# placa1.net
KiCad netlist of a schematic drawn in Altium Designer
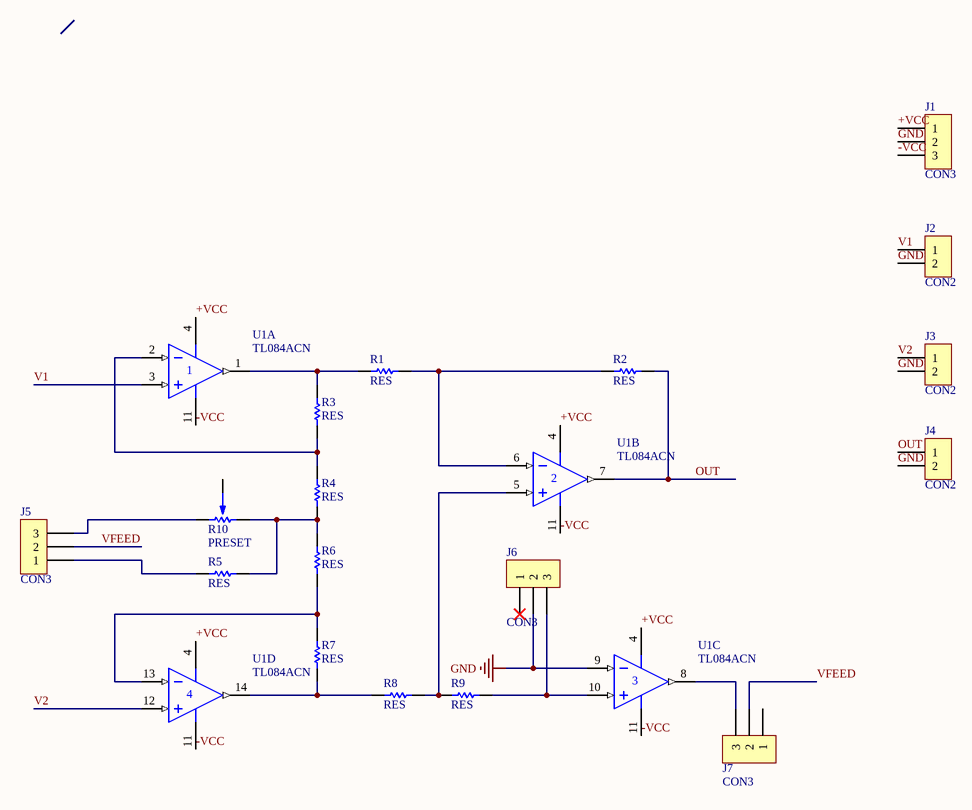
[diagram p0: placa1.SchDoc]

(export (version "E")
  (design (tool "Eeschema 10.0.6"))
  (components
    (comp (ref "J1") (value "CON3") (footprint "SIP3") (libsource (lib "LIBEBAL") (part "CON3")))
    (comp (ref "J2") (value "CON2") (footprint "SIP2") (libsource (lib "LIBEBAL") (part "CON2")))
    (comp (ref "J3") (value "CON2") (footprint "SIP2") (libsource (lib "LIBEBAL") (part "CON2")))
    (comp (ref "J4") (value "CON2") (footprint "SIP2") (libsource (lib "LIBEBAL") (part "CON2")))
    (comp (ref "J5") (value "CON3") (footprint "SIP3") (libsource (lib "") (part "CON3_2")))
    (comp (ref "J6") (value "CON3") (footprint "SIP3") (libsource (lib "") (part "CON3_3")))
    (comp (ref "J7") (value "CON3") (footprint "SIP3") (libsource (lib "") (part "CON3_1")))
    (comp (ref "R1") (value "RES") (footprint "0805") (libsource (lib "LIBEBAL") (part "RES")))
    (comp (ref "R2") (value "RES") (footprint "0805") (libsource (lib "LIBEBAL") (part "RES")))
    (comp (ref "R3") (value "RES") (footprint "0805") (libsource (lib "LIBEBAL") (part "RES")))
    (comp (ref "R4") (value "RES") (footprint "0805") (libsource (lib "LIBEBAL") (part "RES")))
    (comp (ref "R5") (value "RES") (footprint "0805") (libsource (lib "LIBEBAL") (part "RES")))
    (comp (ref "R6") (value "RES") (footprint "0805") (libsource (lib "LIBEBAL") (part "RES")))
    (comp (ref "R7") (value "RES") (footprint "0805") (libsource (lib "LIBEBAL") (part "RES")))
    (comp (ref "R8") (value "RES") (footprint "0805") (libsource (lib "LIBEBAL") (part "RES")))
    (comp (ref "R9") (value "RES") (footprint "0805") (libsource (lib "LIBEBAL") (part "RES")))
    (comp (ref "R10") (value "PRESET") (footprint "PRESET V") (libsource (lib "LIBEBAL") (part "PRESET")))
    (comp (ref "U1")
      (value "TL084ACN")
      (footprint "646-06")
      (description "JFET-Input Operational Amplifier")
      (fields (field (name "PUBLISHER") "Altium Limited"))
      (libsource (lib "Motorola Amplifier Operational Amplifier") (part "TL084ACN"))
    )
  )
  (nets
    (net (code "1") (name "/+VCC") (class "Default")
      (node (ref "J1") (pin "1") (pinfunction "1_1") (pintype "passive"))
      (node (ref "U1") (pin "4") (pinfunction "V+_4") (pintype "power_in"))
    )
    (net (code "2") (name "/-VCC") (class "Default")
      (node (ref "J1") (pin "3") (pinfunction "3_3") (pintype "passive"))
      (node (ref "U1") (pin "11") (pinfunction "V-_11") (pintype "power_in"))
    )
    (net (code "3") (name "/OUT") (class "Default")
      (node (ref "J4") (pin "1") (pinfunction "1_1") (pintype "passive"))
      (node (ref "R2") (pin "2") (pinfunction "2_2") (pintype "passive"))
      (node (ref "U1") (pin "7") (pinfunction "OUT_7") (pintype "output"))
    )
    (net (code "4") (name "/V1") (class "Default")
      (node (ref "J2") (pin "1") (pinfunction "1_1") (pintype "passive"))
      (node (ref "U1") (pin "3") (pinfunction "IN+_3") (pintype "input"))
    )
    (net (code "5") (name "/V2") (class "Default")
      (node (ref "J3") (pin "1") (pinfunction "1_1") (pintype "passive"))
      (node (ref "U1") (pin "12") (pinfunction "IN+_12") (pintype "input"))
    )
    (net (code "6") (name "/VFEED") (class "Default")
      (node (ref "J5") (pin "2") (pinfunction "2_2") (pintype "passive"))
      (node (ref "J7") (pin "2") (pinfunction "2_2") (pintype "passive"))
    )
    (net (code "7") (name "GND") (class "Default")
      (node (ref "J1") (pin "2") (pinfunction "2_2") (pintype "passive"))
      (node (ref "J2") (pin "2") (pinfunction "2_2") (pintype "passive"))
      (node (ref "J3") (pin "2") (pinfunction "2_2") (pintype "passive"))
      (node (ref "J4") (pin "2") (pinfunction "2_2") (pintype "passive"))
      (node (ref "J6") (pin "2") (pinfunction "2_2") (pintype "passive"))
      (node (ref "U1") (pin "9") (pinfunction "IN-_9") (pintype "input"))
    )
    (net (code "8") (name "Net-(J5-Pad1)") (class "Default")
      (node (ref "J5") (pin "1") (pinfunction "1_1") (pintype "passive"))
      (node (ref "R5") (pin "1") (pinfunction "1_1") (pintype "passive"))
    )
    (net (code "9") (name "Net-(J5-Pad3)") (class "Default")
      (node (ref "J5") (pin "3") (pinfunction "3_3") (pintype "passive"))
      (node (ref "R10") (pin "1") (pinfunction "1_1") (pintype "passive"))
    )
    (net (code "10") (name "Net-(R10-Pad3)") (class "Default")
      (node (ref "R10") (pin "3") (pinfunction "3_3") (pintype "passive"))
      (node (ref "R4") (pin "1") (pinfunction "1_1") (pintype "passive"))
      (node (ref "R5") (pin "2") (pinfunction "2_2") (pintype "passive"))
      (node (ref "R6") (pin "2") (pinfunction "2_2") (pintype "passive"))
    )
    (net (code "11") (name "Net-(U1A-IN-)") (class "Default")
      (node (ref "R3") (pin "1") (pinfunction "1_1") (pintype "passive"))
      (node (ref "R4") (pin "2") (pinfunction "2_2") (pintype "passive"))
      (node (ref "U1") (pin "2") (pinfunction "IN-_2") (pintype "input"))
    )
    (net (code "12") (name "Net-(U1A-OUT)") (class "Default")
      (node (ref "R1") (pin "1") (pinfunction "1_1") (pintype "passive"))
      (node (ref "R3") (pin "2") (pinfunction "2_2") (pintype "passive"))
      (node (ref "U1") (pin "1") (pinfunction "OUT_1") (pintype "output"))
    )
    (net (code "13") (name "Net-(U1B-IN+)") (class "Default")
      (node (ref "R8") (pin "2") (pinfunction "2_2") (pintype "passive"))
      (node (ref "R9") (pin "1") (pinfunction "1_1") (pintype "passive"))
      (node (ref "U1") (pin "5") (pinfunction "IN+_5") (pintype "input"))
    )
    (net (code "14") (name "Net-(U1B-IN-)") (class "Default")
      (node (ref "R1") (pin "2") (pinfunction "2_2") (pintype "passive"))
      (node (ref "R2") (pin "1") (pinfunction "1_1") (pintype "passive"))
      (node (ref "U1") (pin "6") (pinfunction "IN-_6") (pintype "input"))
    )
    (net (code "15") (name "Net-(U1C-IN+)") (class "Default")
      (node (ref "J6") (pin "3") (pinfunction "3_3") (pintype "passive"))
      (node (ref "R9") (pin "2") (pinfunction "2_2") (pintype "passive"))
      (node (ref "U1") (pin "10") (pinfunction "IN+_10") (pintype "input"))
    )
    (net (code "16") (name "Net-(U1C-OUT)") (class "Default")
      (node (ref "J7") (pin "3") (pinfunction "3_3") (pintype "passive"))
      (node (ref "U1") (pin "8") (pinfunction "OUT_8") (pintype "output"))
    )
    (net (code "17") (name "Net-(U1D-IN-)") (class "Default")
      (node (ref "R6") (pin "1") (pinfunction "1_1") (pintype "passive"))
      (node (ref "R7") (pin "2") (pinfunction "2_2") (pintype "passive"))
      (node (ref "U1") (pin "13") (pinfunction "IN-_13") (pintype "input"))
    )
    (net (code "18") (name "Net-(U1D-OUT)") (class "Default")
      (node (ref "R7") (pin "1") (pinfunction "1_1") (pintype "passive"))
      (node (ref "R8") (pin "1") (pinfunction "1_1") (pintype "passive"))
      (node (ref "U1") (pin "14") (pinfunction "OUT_14") (pintype "output"))
    )
    (net (code "19") (name "unconnected-(J6-Pad1)") (class "Default")
      (node (ref "J6") (pin "1") (pinfunction "1_1") (pintype "passive+no_connect"))
    )
    (net (code "20") (name "unconnected-(J7-Pad1)") (class "Default")
      (node (ref "J7") (pin "1") (pinfunction "1_1") (pintype "passive"))
    )
    (net (code "21") (name "unconnected-(R10-Pad2)") (class "Default")
      (node (ref "R10") (pin "2") (pinfunction "2_2") (pintype "passive"))
    )
  )
)
